# Hall_Sensor.net
KiCad netlist of a schematic drawn in EAGLE
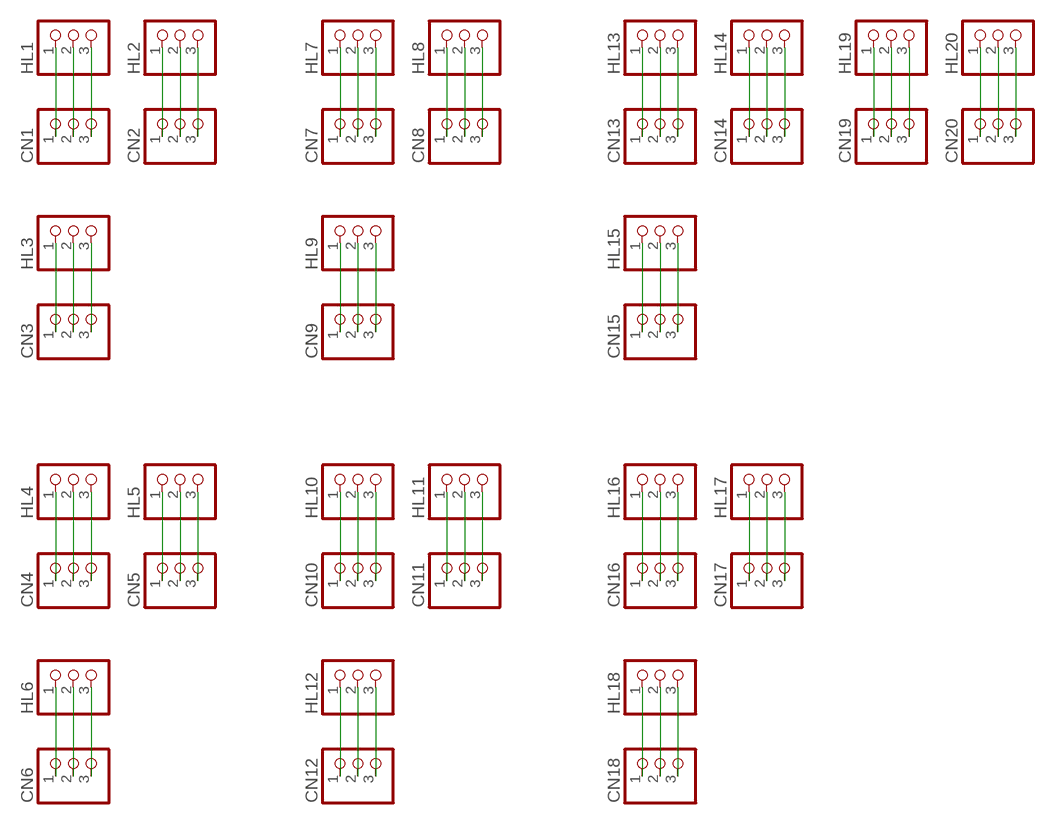
[diagram p0: schematic, sheet 1]

(export (version "E")
  (design (tool "Eeschema 10.0.6"))
  (components
    (comp (ref "CN1")
      (value "PINHD-1X3")
      (footprint "eagle-import:1X03")
      (libsource (lib "eagle-import") (part "PINHD-1X3"))
    )
    (comp (ref "CN2")
      (value "PINHD-1X3")
      (footprint "eagle-import:1X03")
      (libsource (lib "eagle-import") (part "PINHD-1X3"))
    )
    (comp (ref "CN3")
      (value "PINHD-1X3")
      (footprint "eagle-import:1X03")
      (libsource (lib "eagle-import") (part "PINHD-1X3"))
    )
    (comp (ref "CN4")
      (value "PINHD-1X3")
      (footprint "eagle-import:1X03")
      (libsource (lib "eagle-import") (part "PINHD-1X3"))
    )
    (comp (ref "CN5")
      (value "PINHD-1X3")
      (footprint "eagle-import:1X03")
      (libsource (lib "eagle-import") (part "PINHD-1X3"))
    )
    (comp (ref "CN6")
      (value "PINHD-1X3")
      (footprint "eagle-import:1X03")
      (libsource (lib "eagle-import") (part "PINHD-1X3"))
    )
    (comp (ref "CN7")
      (value "PINHD-1X3")
      (footprint "eagle-import:1X03")
      (libsource (lib "eagle-import") (part "PINHD-1X3"))
    )
    (comp (ref "CN8")
      (value "PINHD-1X3")
      (footprint "eagle-import:1X03")
      (libsource (lib "eagle-import") (part "PINHD-1X3"))
    )
    (comp (ref "CN9")
      (value "PINHD-1X3")
      (footprint "eagle-import:1X03")
      (libsource (lib "eagle-import") (part "PINHD-1X3"))
    )
    (comp (ref "CN10")
      (value "PINHD-1X3")
      (footprint "eagle-import:1X03")
      (libsource (lib "eagle-import") (part "PINHD-1X3"))
    )
    (comp (ref "CN11")
      (value "PINHD-1X3")
      (footprint "eagle-import:1X03")
      (libsource (lib "eagle-import") (part "PINHD-1X3"))
    )
    (comp (ref "CN12")
      (value "PINHD-1X3")
      (footprint "eagle-import:1X03")
      (libsource (lib "eagle-import") (part "PINHD-1X3"))
    )
    (comp (ref "CN13")
      (value "PINHD-1X3")
      (footprint "eagle-import:1X03")
      (libsource (lib "eagle-import") (part "PINHD-1X3"))
    )
    (comp (ref "CN14")
      (value "PINHD-1X3")
      (footprint "eagle-import:1X03")
      (libsource (lib "eagle-import") (part "PINHD-1X3"))
    )
    (comp (ref "CN15")
      (value "PINHD-1X3")
      (footprint "eagle-import:1X03")
      (libsource (lib "eagle-import") (part "PINHD-1X3"))
    )
    (comp (ref "CN16")
      (value "PINHD-1X3")
      (footprint "eagle-import:1X03")
      (libsource (lib "eagle-import") (part "PINHD-1X3"))
    )
    (comp (ref "CN17")
      (value "PINHD-1X3")
      (footprint "eagle-import:1X03")
      (libsource (lib "eagle-import") (part "PINHD-1X3"))
    )
    (comp (ref "CN18")
      (value "PINHD-1X3")
      (footprint "eagle-import:1X03")
      (libsource (lib "eagle-import") (part "PINHD-1X3"))
    )
    (comp (ref "CN19")
      (value "PINHD-1X3")
      (footprint "eagle-import:1X03")
      (libsource (lib "eagle-import") (part "PINHD-1X3"))
    )
    (comp (ref "CN20")
      (value "PINHD-1X3")
      (footprint "eagle-import:1X03")
      (libsource (lib "eagle-import") (part "PINHD-1X3"))
    )
    (comp (ref "HL1")
      (value "PINHD-1X3")
      (footprint "eagle-import:1X03")
      (libsource (lib "eagle-import") (part "PINHD-1X3"))
    )
    (comp (ref "HL2")
      (value "PINHD-1X3")
      (footprint "eagle-import:1X03")
      (libsource (lib "eagle-import") (part "PINHD-1X3"))
    )
    (comp (ref "HL3")
      (value "PINHD-1X3")
      (footprint "eagle-import:1X03")
      (libsource (lib "eagle-import") (part "PINHD-1X3"))
    )
    (comp (ref "HL4")
      (value "PINHD-1X3")
      (footprint "eagle-import:1X03")
      (libsource (lib "eagle-import") (part "PINHD-1X3"))
    )
    (comp (ref "HL5")
      (value "PINHD-1X3")
      (footprint "eagle-import:1X03")
      (libsource (lib "eagle-import") (part "PINHD-1X3"))
    )
    (comp (ref "HL6")
      (value "PINHD-1X3")
      (footprint "eagle-import:1X03")
      (libsource (lib "eagle-import") (part "PINHD-1X3"))
    )
    (comp (ref "HL7")
      (value "PINHD-1X3")
      (footprint "eagle-import:1X03")
      (libsource (lib "eagle-import") (part "PINHD-1X3"))
    )
    (comp (ref "HL8")
      (value "PINHD-1X3")
      (footprint "eagle-import:1X03")
      (libsource (lib "eagle-import") (part "PINHD-1X3"))
    )
    (comp (ref "HL9")
      (value "PINHD-1X3")
      (footprint "eagle-import:1X03")
      (libsource (lib "eagle-import") (part "PINHD-1X3"))
    )
    (comp (ref "HL10")
      (value "PINHD-1X3")
      (footprint "eagle-import:1X03")
      (libsource (lib "eagle-import") (part "PINHD-1X3"))
    )
    (comp (ref "HL11")
      (value "PINHD-1X3")
      (footprint "eagle-import:1X03")
      (libsource (lib "eagle-import") (part "PINHD-1X3"))
    )
    (comp (ref "HL12")
      (value "PINHD-1X3")
      (footprint "eagle-import:1X03")
      (libsource (lib "eagle-import") (part "PINHD-1X3"))
    )
    (comp (ref "HL13")
      (value "PINHD-1X3")
      (footprint "eagle-import:1X03")
      (libsource (lib "eagle-import") (part "PINHD-1X3"))
    )
    (comp (ref "HL14")
      (value "PINHD-1X3")
      (footprint "eagle-import:1X03")
      (libsource (lib "eagle-import") (part "PINHD-1X3"))
    )
    (comp (ref "HL15")
      (value "PINHD-1X3")
      (footprint "eagle-import:1X03")
      (libsource (lib "eagle-import") (part "PINHD-1X3"))
    )
    (comp (ref "HL16")
      (value "PINHD-1X3")
      (footprint "eagle-import:1X03")
      (libsource (lib "eagle-import") (part "PINHD-1X3"))
    )
    (comp (ref "HL17")
      (value "PINHD-1X3")
      (footprint "eagle-import:1X03")
      (libsource (lib "eagle-import") (part "PINHD-1X3"))
    )
    (comp (ref "HL18")
      (value "PINHD-1X3")
      (footprint "eagle-import:1X03")
      (libsource (lib "eagle-import") (part "PINHD-1X3"))
    )
    (comp (ref "HL19")
      (value "PINHD-1X3")
      (footprint "eagle-import:1X03")
      (libsource (lib "eagle-import") (part "PINHD-1X3"))
    )
    (comp (ref "HL20")
      (value "PINHD-1X3")
      (footprint "eagle-import:1X03")
      (libsource (lib "eagle-import") (part "PINHD-1X3"))
    )
  )
  (nets
    (net (code "1") (name "Net-(CN1-Pad1)") (class "Default")
      (node (ref "CN1") (pin "1") (pinfunction "1_1") (pintype "passive"))
      (node (ref "HL1") (pin "1") (pinfunction "1_1") (pintype "passive"))
    )
    (net (code "2") (name "Net-(CN1-Pad2)") (class "Default")
      (node (ref "CN1") (pin "2") (pinfunction "2_2") (pintype "passive"))
      (node (ref "HL1") (pin "2") (pinfunction "2_2") (pintype "passive"))
    )
    (net (code "3") (name "Net-(CN1-Pad3)") (class "Default")
      (node (ref "CN1") (pin "3") (pinfunction "3_3") (pintype "passive"))
      (node (ref "HL1") (pin "3") (pinfunction "3_3") (pintype "passive"))
    )
    (net (code "4") (name "Net-(CN2-Pad1)") (class "Default")
      (node (ref "CN2") (pin "1") (pinfunction "1_1") (pintype "passive"))
      (node (ref "HL2") (pin "1") (pinfunction "1_1") (pintype "passive"))
    )
    (net (code "5") (name "Net-(CN2-Pad2)") (class "Default")
      (node (ref "CN2") (pin "2") (pinfunction "2_2") (pintype "passive"))
      (node (ref "HL2") (pin "2") (pinfunction "2_2") (pintype "passive"))
    )
    (net (code "6") (name "Net-(CN2-Pad3)") (class "Default")
      (node (ref "CN2") (pin "3") (pinfunction "3_3") (pintype "passive"))
      (node (ref "HL2") (pin "3") (pinfunction "3_3") (pintype "passive"))
    )
    (net (code "7") (name "Net-(CN3-Pad1)") (class "Default")
      (node (ref "CN3") (pin "1") (pinfunction "1_1") (pintype "passive"))
      (node (ref "HL3") (pin "1") (pinfunction "1_1") (pintype "passive"))
    )
    (net (code "8") (name "Net-(CN3-Pad2)") (class "Default")
      (node (ref "CN3") (pin "2") (pinfunction "2_2") (pintype "passive"))
      (node (ref "HL3") (pin "2") (pinfunction "2_2") (pintype "passive"))
    )
    (net (code "9") (name "Net-(CN3-Pad3)") (class "Default")
      (node (ref "CN3") (pin "3") (pinfunction "3_3") (pintype "passive"))
      (node (ref "HL3") (pin "3") (pinfunction "3_3") (pintype "passive"))
    )
    (net (code "10") (name "Net-(CN4-Pad1)") (class "Default")
      (node (ref "CN4") (pin "1") (pinfunction "1_1") (pintype "passive"))
      (node (ref "HL4") (pin "1") (pinfunction "1_1") (pintype "passive"))
    )
    (net (code "11") (name "Net-(CN4-Pad2)") (class "Default")
      (node (ref "CN4") (pin "2") (pinfunction "2_2") (pintype "passive"))
      (node (ref "HL4") (pin "2") (pinfunction "2_2") (pintype "passive"))
    )
    (net (code "12") (name "Net-(CN4-Pad3)") (class "Default")
      (node (ref "CN4") (pin "3") (pinfunction "3_3") (pintype "passive"))
      (node (ref "HL4") (pin "3") (pinfunction "3_3") (pintype "passive"))
    )
    (net (code "13") (name "Net-(CN5-Pad1)") (class "Default")
      (node (ref "CN5") (pin "1") (pinfunction "1_1") (pintype "passive"))
      (node (ref "HL5") (pin "1") (pinfunction "1_1") (pintype "passive"))
    )
    (net (code "14") (name "Net-(CN5-Pad2)") (class "Default")
      (node (ref "CN5") (pin "2") (pinfunction "2_2") (pintype "passive"))
      (node (ref "HL5") (pin "2") (pinfunction "2_2") (pintype "passive"))
    )
    (net (code "15") (name "Net-(CN5-Pad3)") (class "Default")
      (node (ref "CN5") (pin "3") (pinfunction "3_3") (pintype "passive"))
      (node (ref "HL5") (pin "3") (pinfunction "3_3") (pintype "passive"))
    )
    (net (code "16") (name "Net-(CN6-Pad1)") (class "Default")
      (node (ref "CN6") (pin "1") (pinfunction "1_1") (pintype "passive"))
      (node (ref "HL6") (pin "1") (pinfunction "1_1") (pintype "passive"))
    )
    (net (code "17") (name "Net-(CN6-Pad2)") (class "Default")
      (node (ref "CN6") (pin "2") (pinfunction "2_2") (pintype "passive"))
      (node (ref "HL6") (pin "2") (pinfunction "2_2") (pintype "passive"))
    )
    (net (code "18") (name "Net-(CN6-Pad3)") (class "Default")
      (node (ref "CN6") (pin "3") (pinfunction "3_3") (pintype "passive"))
      (node (ref "HL6") (pin "3") (pinfunction "3_3") (pintype "passive"))
    )
    (net (code "19") (name "Net-(CN7-Pad1)") (class "Default")
      (node (ref "CN7") (pin "1") (pinfunction "1_1") (pintype "passive"))
      (node (ref "HL7") (pin "1") (pinfunction "1_1") (pintype "passive"))
    )
    (net (code "20") (name "Net-(CN7-Pad2)") (class "Default")
      (node (ref "CN7") (pin "2") (pinfunction "2_2") (pintype "passive"))
      (node (ref "HL7") (pin "2") (pinfunction "2_2") (pintype "passive"))
    )
    (net (code "21") (name "Net-(CN7-Pad3)") (class "Default")
      (node (ref "CN7") (pin "3") (pinfunction "3_3") (pintype "passive"))
      (node (ref "HL7") (pin "3") (pinfunction "3_3") (pintype "passive"))
    )
    (net (code "22") (name "Net-(CN8-Pad1)") (class "Default")
      (node (ref "CN8") (pin "1") (pinfunction "1_1") (pintype "passive"))
      (node (ref "HL8") (pin "1") (pinfunction "1_1") (pintype "passive"))
    )
    (net (code "23") (name "Net-(CN8-Pad2)") (class "Default")
      (node (ref "CN8") (pin "2") (pinfunction "2_2") (pintype "passive"))
      (node (ref "HL8") (pin "2") (pinfunction "2_2") (pintype "passive"))
    )
    (net (code "24") (name "Net-(CN8-Pad3)") (class "Default")
      (node (ref "CN8") (pin "3") (pinfunction "3_3") (pintype "passive"))
      (node (ref "HL8") (pin "3") (pinfunction "3_3") (pintype "passive"))
    )
    (net (code "25") (name "Net-(CN9-Pad1)") (class "Default")
      (node (ref "CN9") (pin "1") (pinfunction "1_1") (pintype "passive"))
      (node (ref "HL9") (pin "1") (pinfunction "1_1") (pintype "passive"))
    )
    (net (code "26") (name "Net-(CN9-Pad2)") (class "Default")
      (node (ref "CN9") (pin "2") (pinfunction "2_2") (pintype "passive"))
      (node (ref "HL9") (pin "2") (pinfunction "2_2") (pintype "passive"))
    )
    (net (code "27") (name "Net-(CN9-Pad3)") (class "Default")
      (node (ref "CN9") (pin "3") (pinfunction "3_3") (pintype "passive"))
      (node (ref "HL9") (pin "3") (pinfunction "3_3") (pintype "passive"))
    )
    (net (code "28") (name "Net-(CN10-Pad1)") (class "Default")
      (node (ref "CN10") (pin "1") (pinfunction "1_1") (pintype "passive"))
      (node (ref "HL10") (pin "1") (pinfunction "1_1") (pintype "passive"))
    )
    (net (code "29") (name "Net-(CN10-Pad2)") (class "Default")
      (node (ref "CN10") (pin "2") (pinfunction "2_2") (pintype "passive"))
      (node (ref "HL10") (pin "2") (pinfunction "2_2") (pintype "passive"))
    )
    (net (code "30") (name "Net-(CN10-Pad3)") (class "Default")
      (node (ref "CN10") (pin "3") (pinfunction "3_3") (pintype "passive"))
      (node (ref "HL10") (pin "3") (pinfunction "3_3") (pintype "passive"))
    )
    (net (code "31") (name "Net-(CN11-Pad1)") (class "Default")
      (node (ref "CN11") (pin "1") (pinfunction "1_1") (pintype "passive"))
      (node (ref "HL11") (pin "1") (pinfunction "1_1") (pintype "passive"))
    )
    (net (code "32") (name "Net-(CN11-Pad2)") (class "Default")
      (node (ref "CN11") (pin "2") (pinfunction "2_2") (pintype "passive"))
      (node (ref "HL11") (pin "2") (pinfunction "2_2") (pintype "passive"))
    )
    (net (code "33") (name "Net-(CN11-Pad3)") (class "Default")
      (node (ref "CN11") (pin "3") (pinfunction "3_3") (pintype "passive"))
      (node (ref "HL11") (pin "3") (pinfunction "3_3") (pintype "passive"))
    )
    (net (code "34") (name "Net-(CN12-Pad1)") (class "Default")
      (node (ref "CN12") (pin "1") (pinfunction "1_1") (pintype "passive"))
      (node (ref "HL12") (pin "1") (pinfunction "1_1") (pintype "passive"))
    )
    (net (code "35") (name "Net-(CN12-Pad2)") (class "Default")
      (node (ref "CN12") (pin "2") (pinfunction "2_2") (pintype "passive"))
      (node (ref "HL12") (pin "2") (pinfunction "2_2") (pintype "passive"))
    )
    (net (code "36") (name "Net-(CN12-Pad3)") (class "Default")
      (node (ref "CN12") (pin "3") (pinfunction "3_3") (pintype "passive"))
      (node (ref "HL12") (pin "3") (pinfunction "3_3") (pintype "passive"))
    )
    (net (code "37") (name "Net-(CN13-Pad1)") (class "Default")
      (node (ref "CN13") (pin "1") (pinfunction "1_1") (pintype "passive"))
      (node (ref "HL13") (pin "1") (pinfunction "1_1") (pintype "passive"))
    )
    (net (code "38") (name "Net-(CN13-Pad2)") (class "Default")
      (node (ref "CN13") (pin "2") (pinfunction "2_2") (pintype "passive"))
      (node (ref "HL13") (pin "2") (pinfunction "2_2") (pintype "passive"))
    )
    (net (code "39") (name "Net-(CN13-Pad3)") (class "Default")
      (node (ref "CN13") (pin "3") (pinfunction "3_3") (pintype "passive"))
      (node (ref "HL13") (pin "3") (pinfunction "3_3") (pintype "passive"))
    )
    (net (code "40") (name "Net-(CN14-Pad1)") (class "Default")
      (node (ref "CN14") (pin "1") (pinfunction "1_1") (pintype "passive"))
      (node (ref "HL14") (pin "1") (pinfunction "1_1") (pintype "passive"))
    )
    (net (code "41") (name "Net-(CN14-Pad2)") (class "Default")
      (node (ref "CN14") (pin "2") (pinfunction "2_2") (pintype "passive"))
      (node (ref "HL14") (pin "2") (pinfunction "2_2") (pintype "passive"))
    )
    (net (code "42") (name "Net-(CN14-Pad3)") (class "Default")
      (node (ref "CN14") (pin "3") (pinfunction "3_3") (pintype "passive"))
      (node (ref "HL14") (pin "3") (pinfunction "3_3") (pintype "passive"))
    )
    (net (code "43") (name "Net-(CN15-Pad1)") (class "Default")
      (node (ref "CN15") (pin "1") (pinfunction "1_1") (pintype "passive"))
      (node (ref "HL15") (pin "1") (pinfunction "1_1") (pintype "passive"))
    )
    (net (code "44") (name "Net-(CN15-Pad2)") (class "Default")
      (node (ref "CN15") (pin "2") (pinfunction "2_2") (pintype "passive"))
      (node (ref "HL15") (pin "2") (pinfunction "2_2") (pintype "passive"))
    )
    (net (code "45") (name "Net-(CN15-Pad3)") (class "Default")
      (node (ref "CN15") (pin "3") (pinfunction "3_3") (pintype "passive"))
      (node (ref "HL15") (pin "3") (pinfunction "3_3") (pintype "passive"))
    )
    (net (code "46") (name "Net-(CN16-Pad1)") (class "Default")
      (node (ref "CN16") (pin "1") (pinfunction "1_1") (pintype "passive"))
      (node (ref "HL16") (pin "1") (pinfunction "1_1") (pintype "passive"))
    )
    (net (code "47") (name "Net-(CN16-Pad2)") (class "Default")
      (node (ref "CN16") (pin "2") (pinfunction "2_2") (pintype "passive"))
      (node (ref "HL16") (pin "2") (pinfunction "2_2") (pintype "passive"))
    )
    (net (code "48") (name "Net-(CN16-Pad3)") (class "Default")
      (node (ref "CN16") (pin "3") (pinfunction "3_3") (pintype "passive"))
      (node (ref "HL16") (pin "3") (pinfunction "3_3") (pintype "passive"))
    )
    (net (code "49") (name "Net-(CN17-Pad1)") (class "Default")
      (node (ref "CN17") (pin "1") (pinfunction "1_1") (pintype "passive"))
      (node (ref "HL17") (pin "1") (pinfunction "1_1") (pintype "passive"))
    )
    (net (code "50") (name "Net-(CN17-Pad2)") (class "Default")
      (node (ref "CN17") (pin "2") (pinfunction "2_2") (pintype "passive"))
      (node (ref "HL17") (pin "2") (pinfunction "2_2") (pintype "passive"))
    )
    (net (code "51") (name "Net-(CN17-Pad3)") (class "Default")
      (node (ref "CN17") (pin "3") (pinfunction "3_3") (pintype "passive"))
      (node (ref "HL17") (pin "3") (pinfunction "3_3") (pintype "passive"))
    )
    (net (code "52") (name "Net-(CN18-Pad1)") (class "Default")
      (node (ref "CN18") (pin "1") (pinfunction "1_1") (pintype "passive"))
      (node (ref "HL18") (pin "1") (pinfunction "1_1") (pintype "passive"))
    )
    (net (code "53") (name "Net-(CN18-Pad2)") (class "Default")
      (node (ref "CN18") (pin "2") (pinfunction "2_2") (pintype "passive"))
      (node (ref "HL18") (pin "2") (pinfunction "2_2") (pintype "passive"))
    )
    (net (code "54") (name "Net-(CN18-Pad3)") (class "Default")
      (node (ref "CN18") (pin "3") (pinfunction "3_3") (pintype "passive"))
      (node (ref "HL18") (pin "3") (pinfunction "3_3") (pintype "passive"))
    )
    (net (code "55") (name "Net-(CN19-Pad1)") (class "Default")
      (node (ref "CN19") (pin "1") (pinfunction "1_1") (pintype "passive"))
      (node (ref "HL19") (pin "1") (pinfunction "1_1") (pintype "passive"))
    )
    (net (code "56") (name "Net-(CN19-Pad2)") (class "Default")
      (node (ref "CN19") (pin "2") (pinfunction "2_2") (pintype "passive"))
      (node (ref "HL19") (pin "2") (pinfunction "2_2") (pintype "passive"))
    )
    (net (code "57") (name "Net-(CN19-Pad3)") (class "Default")
      (node (ref "CN19") (pin "3") (pinfunction "3_3") (pintype "passive"))
      (node (ref "HL19") (pin "3") (pinfunction "3_3") (pintype "passive"))
    )
    (net (code "58") (name "Net-(CN20-Pad1)") (class "Default")
      (node (ref "CN20") (pin "1") (pinfunction "1_1") (pintype "passive"))
      (node (ref "HL20") (pin "1") (pinfunction "1_1") (pintype "passive"))
    )
    (net (code "59") (name "Net-(CN20-Pad2)") (class "Default")
      (node (ref "CN20") (pin "2") (pinfunction "2_2") (pintype "passive"))
      (node (ref "HL20") (pin "2") (pinfunction "2_2") (pintype "passive"))
    )
    (net (code "60") (name "Net-(CN20-Pad3)") (class "Default")
      (node (ref "CN20") (pin "3") (pinfunction "3_3") (pintype "passive"))
      (node (ref "HL20") (pin "3") (pinfunction "3_3") (pintype "passive"))
    )
  )
)
